# etrx357-redone.net
KiCad netlist of a schematic drawn in EAGLE
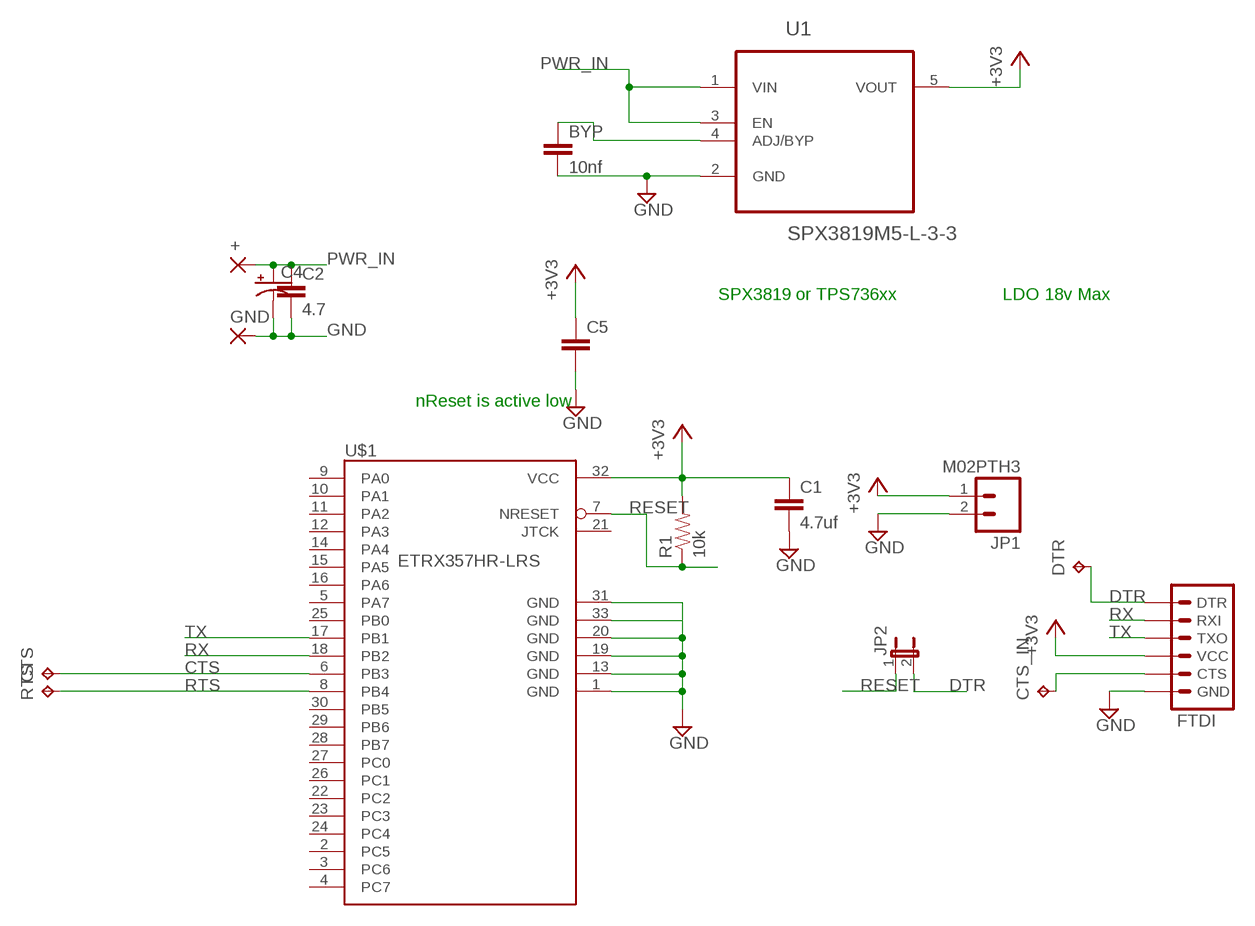
[diagram p0: schematic, sheet 1]

(export (version "E")
  (design (tool "Eeschema 10.0.6"))
  (components
    (comp (ref "+")
      (value "3,17/1,3")
      (footprint "eagle-import:3,17_1,3")
      (libsource (lib "eagle-import") (part "3,17/1,3"))
    )
    (comp (ref "BYP")
      (value "10nf")
      (footprint "eagle-import:0603-CAP")
      (libsource (lib "eagle-import") (part "CAP0603-CAP"))
    )
    (comp (ref "C1")
      (value "4.7uf")
      (footprint "eagle-import:0603-CAP")
      (libsource (lib "eagle-import") (part "CAP0603-CAP"))
    )
    (comp (ref "C2")
      (value "4.7")
      (footprint "eagle-import:0603-CAP")
      (libsource (lib "eagle-import") (part "CAP0603-CAP"))
    )
    (comp (ref "C4")
      (value "CAP_POLPTH1")
      (footprint "eagle-import:CPOL-RADIAL-100UF-25V")
      (libsource (lib "eagle-import") (part "CAP_POLPTH1"))
    )
    (comp (ref "C5")
      (value "CAPPTH")
      (footprint "eagle-import:CAP-PTH-SMALL")
      (libsource (lib "eagle-import") (part "CAPPTH"))
    )
    (comp (ref "CTS")
      (value "TPTP20R")
      (footprint "eagle-import:TP20R")
      (libsource (lib "eagle-import") (part "TPTP20R"))
    )
    (comp (ref "CTS_IN")
      (value "TPTP20R")
      (footprint "eagle-import:TP20R")
      (libsource (lib "eagle-import") (part "TPTP20R"))
    )
    (comp (ref "DTR")
      (value "TPTP20R")
      (footprint "eagle-import:TP20R")
      (libsource (lib "eagle-import") (part "TPTP20R"))
    )
    (comp (ref "FTDI")
      (value "ARDUINO_SERIAL_PROGRAMPTH")
      (footprint "eagle-import:1X06")
      (libsource (lib "eagle-import") (part "ARDUINO_SERIAL_PROGRAMPTH"))
    )
    (comp (ref "GND")
      (value "3,17/1,3")
      (footprint "eagle-import:3,17_1,3")
      (libsource (lib "eagle-import") (part "3,17/1,3"))
    )
    (comp (ref "JP1")
      (value "M02PTH3")
      (footprint "eagle-import:1X02_LONGPADS")
      (libsource (lib "eagle-import") (part "M02PTH3"))
    )
    (comp (ref "JP2")
      (value "JUMPER-2-OLDSMD-NO")
      (footprint "eagle-import:SJ_2S-NO")
      (libsource (lib "eagle-import") (part "JUMPER-2-OLDSMD-NO"))
    )
    (comp (ref "R1")
      (value "10k")
      (footprint "eagle-import:0603-RES")
      (libsource (lib "eagle-import") (part "RESISTOR0603-RES"))
    )
    (comp (ref "RTS")
      (value "TPTP20R")
      (footprint "eagle-import:TP20R")
      (libsource (lib "eagle-import") (part "TPTP20R"))
    )
    (comp (ref "U$1")
      (value "ETRX357HR-LRS")
      (footprint "eagle-import:ETRX3")
      (libsource (lib "eagle-import") (part "ETRX357HR-LRS"))
    )
    (comp (ref "U1")
      (value "SPX3819M5-L-3-3")
      (footprint "eagle-import:SOT95P280X145-5N")
      (libsource (lib "eagle-import") (part "SPX3819M5-L-3-3"))
    )
  )
  (nets
    (net (code "1") (name "+3V3") (class "Default")
      (node (ref "C1") (pin "1") (pinfunction "1_1") (pintype "passive"))
      (node (ref "C5") (pin "1") (pinfunction "1_1") (pintype "passive"))
      (node (ref "FTDI") (pin "4") (pinfunction "VCC_4") (pintype "passive"))
      (node (ref "JP1") (pin "1") (pinfunction "1_1") (pintype "passive"))
      (node (ref "R1") (pin "2") (pinfunction "2_2") (pintype "passive"))
      (node (ref "U$1") (pin "32") (pinfunction "VCC_32") (pintype "power_in"))
      (node (ref "U1") (pin "5") (pinfunction "VOUT_5") (pintype "output"))
    )
    (net (code "2") (name "/CTS") (class "Default")
      (node (ref "CTS") (pin "TP") (pinfunction "TP_TP") (pintype "input"))
      (node (ref "U$1") (pin "6") (pinfunction "PB3_6") (pintype "bidirectional"))
    )
    (net (code "3") (name "/DTR") (class "Default")
      (node (ref "DTR") (pin "TP") (pinfunction "TP_TP") (pintype "input"))
      (node (ref "FTDI") (pin "1") (pinfunction "DTR_1") (pintype "passive"))
      (node (ref "JP2") (pin "2") (pinfunction "2_2") (pintype "passive"))
    )
    (net (code "4") (name "/PWR_IN") (class "Default")
      (node (ref "+") (pin "1") (pinfunction "P_1") (pintype "passive"))
      (node (ref "C2") (pin "1") (pinfunction "1_1") (pintype "passive"))
      (node (ref "C4") (pin "1") (pinfunction "+_1") (pintype "passive"))
      (node (ref "U1") (pin "1") (pinfunction "VIN_1") (pintype "power_in"))
      (node (ref "U1") (pin "3") (pinfunction "EN_3") (pintype "input"))
    )
    (net (code "5") (name "/RESET") (class "Default")
      (node (ref "JP2") (pin "1") (pinfunction "1_1") (pintype "passive"))
      (node (ref "R1") (pin "1") (pinfunction "1_1") (pintype "passive"))
      (node (ref "U$1") (pin "7") (pinfunction "NRESET_7") (pintype "bidirectional"))
    )
    (net (code "6") (name "/RTS") (class "Default")
      (node (ref "RTS") (pin "TP") (pinfunction "TP_TP") (pintype "input"))
      (node (ref "U$1") (pin "8") (pinfunction "PB4_8") (pintype "bidirectional"))
    )
    (net (code "7") (name "/RX") (class "Default")
      (node (ref "FTDI") (pin "2") (pinfunction "RXI_2") (pintype "passive"))
      (node (ref "U$1") (pin "18") (pinfunction "PB2_18") (pintype "bidirectional"))
    )
    (net (code "8") (name "/TX") (class "Default")
      (node (ref "FTDI") (pin "3") (pinfunction "TXO_3") (pintype "passive"))
      (node (ref "U$1") (pin "17") (pinfunction "PB1_17") (pintype "bidirectional"))
    )
    (net (code "9") (name "GND") (class "Default")
      (node (ref "BYP") (pin "2") (pinfunction "2_2") (pintype "passive"))
      (node (ref "C1") (pin "2") (pinfunction "2_2") (pintype "passive"))
      (node (ref "C2") (pin "2") (pinfunction "2_2") (pintype "passive"))
      (node (ref "C4") (pin "2") (pinfunction "-_2") (pintype "passive"))
      (node (ref "C5") (pin "2") (pinfunction "2_2") (pintype "passive"))
      (node (ref "FTDI") (pin "6") (pinfunction "GND_6") (pintype "passive"))
      (node (ref "GND") (pin "1") (pinfunction "P_1") (pintype "passive"))
      (node (ref "JP1") (pin "2") (pinfunction "2_2") (pintype "passive"))
      (node (ref "U$1") (pin "1") (pinfunction "GND_1") (pintype "power_in"))
      (node (ref "U$1") (pin "13") (pinfunction "GND_13") (pintype "power_in"))
      (node (ref "U$1") (pin "19") (pinfunction "GND_19") (pintype "power_in"))
      (node (ref "U$1") (pin "20") (pinfunction "GND_20") (pintype "power_in"))
      (node (ref "U$1") (pin "31") (pinfunction "GND_31") (pintype "power_in"))
      (node (ref "U$1") (pin "33") (pinfunction "GND_33") (pintype "power_in"))
      (node (ref "U1") (pin "2") (pinfunction "GND_2") (pintype "passive"))
    )
    (net (code "10") (name "Net-(FTDI-CTS)") (class "Default")
      (node (ref "CTS_IN") (pin "TP") (pinfunction "TP_TP") (pintype "input"))
      (node (ref "FTDI") (pin "5") (pinfunction "CTS_5") (pintype "passive"))
    )
    (net (code "11") (name "Net-(U1-ADJ{slash}BYP)") (class "Default")
      (node (ref "BYP") (pin "1") (pinfunction "1_1") (pintype "passive"))
      (node (ref "U1") (pin "4") (pinfunction "ADJ/BYP_4") (pintype "passive"))
    )
    (net (code "12") (name "unconnected-(U$1-JTCK-Pad21)") (class "Default")
      (node (ref "U$1") (pin "21") (pinfunction "JTCK_21") (pintype "bidirectional"))
    )
    (net (code "13") (name "unconnected-(U$1-PA0-Pad9)") (class "Default")
      (node (ref "U$1") (pin "9") (pinfunction "PA0_9") (pintype "bidirectional"))
    )
    (net (code "14") (name "unconnected-(U$1-PA1-Pad10)") (class "Default")
      (node (ref "U$1") (pin "10") (pinfunction "PA1_10") (pintype "bidirectional"))
    )
    (net (code "15") (name "unconnected-(U$1-PA2-Pad11)") (class "Default")
      (node (ref "U$1") (pin "11") (pinfunction "PA2_11") (pintype "bidirectional"))
    )
    (net (code "16") (name "unconnected-(U$1-PA3-Pad12)") (class "Default")
      (node (ref "U$1") (pin "12") (pinfunction "PA3_12") (pintype "bidirectional"))
    )
    (net (code "17") (name "unconnected-(U$1-PA4-Pad14)") (class "Default")
      (node (ref "U$1") (pin "14") (pinfunction "PA4_14") (pintype "bidirectional"))
    )
    (net (code "18") (name "unconnected-(U$1-PA5-Pad15)") (class "Default")
      (node (ref "U$1") (pin "15") (pinfunction "PA5_15") (pintype "bidirectional"))
    )
    (net (code "19") (name "unconnected-(U$1-PA6-Pad16)") (class "Default")
      (node (ref "U$1") (pin "16") (pinfunction "PA6_16") (pintype "bidirectional"))
    )
    (net (code "20") (name "unconnected-(U$1-PA7-Pad5)") (class "Default")
      (node (ref "U$1") (pin "5") (pinfunction "PA7_5") (pintype "bidirectional"))
    )
    (net (code "21") (name "unconnected-(U$1-PB0-Pad25)") (class "Default")
      (node (ref "U$1") (pin "25") (pinfunction "PB0_25") (pintype "bidirectional"))
    )
    (net (code "22") (name "unconnected-(U$1-PB5-Pad30)") (class "Default")
      (node (ref "U$1") (pin "30") (pinfunction "PB5_30") (pintype "bidirectional"))
    )
    (net (code "23") (name "unconnected-(U$1-PB6-Pad29)") (class "Default")
      (node (ref "U$1") (pin "29") (pinfunction "PB6_29") (pintype "bidirectional"))
    )
    (net (code "24") (name "unconnected-(U$1-PB7-Pad28)") (class "Default")
      (node (ref "U$1") (pin "28") (pinfunction "PB7_28") (pintype "bidirectional"))
    )
    (net (code "25") (name "unconnected-(U$1-PC0-Pad27)") (class "Default")
      (node (ref "U$1") (pin "27") (pinfunction "PC0_27") (pintype "bidirectional"))
    )
    (net (code "26") (name "unconnected-(U$1-PC1-Pad26)") (class "Default")
      (node (ref "U$1") (pin "26") (pinfunction "PC1_26") (pintype "bidirectional"))
    )
    (net (code "27") (name "unconnected-(U$1-PC2-Pad22)") (class "Default")
      (node (ref "U$1") (pin "22") (pinfunction "PC2_22") (pintype "bidirectional"))
    )
    (net (code "28") (name "unconnected-(U$1-PC3-Pad23)") (class "Default")
      (node (ref "U$1") (pin "23") (pinfunction "PC3_23") (pintype "bidirectional"))
    )
    (net (code "29") (name "unconnected-(U$1-PC4-Pad24)") (class "Default")
      (node (ref "U$1") (pin "24") (pinfunction "PC4_24") (pintype "bidirectional"))
    )
    (net (code "30") (name "unconnected-(U$1-PC5-Pad2)") (class "Default")
      (node (ref "U$1") (pin "2") (pinfunction "PC5_2") (pintype "bidirectional"))
    )
    (net (code "31") (name "unconnected-(U$1-PC6-Pad3)") (class "Default")
      (node (ref "U$1") (pin "3") (pinfunction "PC6_3") (pintype "bidirectional"))
    )
    (net (code "32") (name "unconnected-(U$1-PC7-Pad4)") (class "Default")
      (node (ref "U$1") (pin "4") (pinfunction "PC7_4") (pintype "bidirectional"))
    )
  )
)
